# led_nightlight.net
KiCad netlist of a schematic drawn in EAGLE
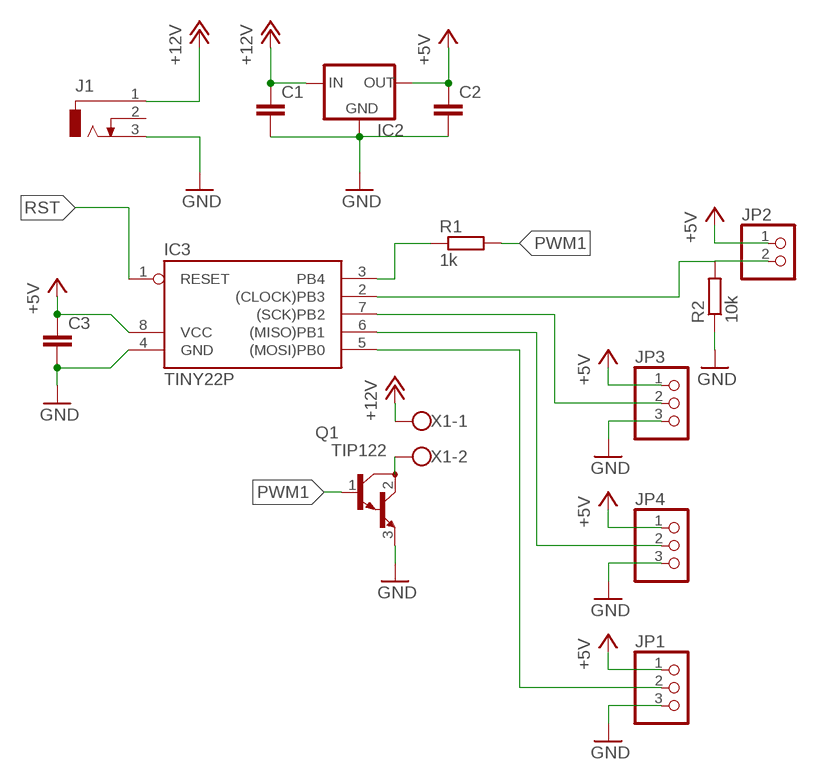
[diagram p0: schematic, sheet 1]

(export (version "E")
  (design (tool "Eeschema 10.0.6"))
  (components
    (comp (ref "C1")
      (value "C-EU025-024X044")
      (footprint "eagle-import:C025-024X044")
      (libsource (lib "eagle-import") (part "C-EU025-024X044"))
    )
    (comp (ref "C2")
      (value "C-EU025-024X044")
      (footprint "eagle-import:C025-024X044")
      (libsource (lib "eagle-import") (part "C-EU025-024X044"))
    )
    (comp (ref "C3")
      (value "C-EU025-024X044")
      (footprint "eagle-import:C025-024X044")
      (libsource (lib "eagle-import") (part "C-EU025-024X044"))
    )
    (comp (ref "IC2")
      (value "78XXL")
      (footprint "eagle-import:78XXL")
      (libsource (lib "eagle-import") (part "78XXL"))
    )
    (comp (ref "IC3")
      (value "TINY22P")
      (footprint "eagle-import:DIL08")
      (libsource (lib "eagle-import") (part "TINY22P"))
    )
    (comp (ref "J1")
      (value "DCJ0303")
      (footprint "eagle-import:DCJ0303")
      (libsource (lib "eagle-import") (part "DCJ0303"))
    )
    (comp (ref "JP1")
      (value "PINHD-1X3")
      (footprint "eagle-import:1X03")
      (libsource (lib "eagle-import") (part "PINHD-1X3"))
    )
    (comp (ref "JP2")
      (value "PINHD-1X2")
      (footprint "eagle-import:1X02")
      (libsource (lib "eagle-import") (part "PINHD-1X2"))
    )
    (comp (ref "JP3")
      (value "PINHD-1X3")
      (footprint "eagle-import:1X03")
      (libsource (lib "eagle-import") (part "PINHD-1X3"))
    )
    (comp (ref "JP4")
      (value "PINHD-1X3")
      (footprint "eagle-import:1X03")
      (libsource (lib "eagle-import") (part "PINHD-1X3"))
    )
    (comp (ref "Q1")
      (value "TIP122")
      (footprint "eagle-import:TO220")
      (libsource (lib "eagle-import") (part "TIP122"))
    )
    (comp (ref "R1")
      (value "1k")
      (footprint "eagle-import:0207_10")
      (libsource (lib "eagle-import") (part "R-EU_0207/10"))
    )
    (comp (ref "R2")
      (value "10k")
      (footprint "eagle-import:0207_10")
      (libsource (lib "eagle-import") (part "R-EU_0207/10"))
    )
    (comp (ref "X1")
      (value "W237-102")
      (footprint "eagle-import:W237-102")
      (fields (field (name "MPN") "237-102"))
      (libsource (lib "eagle-import") (part "W237-102"))
    )
  )
  (nets
    (net (code "1") (name "+5V") (class "Default")
      (node (ref "C2") (pin "1") (pinfunction "1_1") (pintype "passive"))
      (node (ref "C3") (pin "1") (pinfunction "1_1") (pintype "passive"))
      (node (ref "IC2") (pin "OUT") (pinfunction "OUT_OUT") (pintype "passive"))
      (node (ref "IC3") (pin "8") (pinfunction "VCC_8") (pintype "power_in"))
      (node (ref "JP1") (pin "1") (pinfunction "1_1") (pintype "passive"))
      (node (ref "JP2") (pin "1") (pinfunction "1_1") (pintype "passive"))
      (node (ref "JP3") (pin "1") (pinfunction "1_1") (pintype "passive"))
      (node (ref "JP4") (pin "1") (pinfunction "1_1") (pintype "passive"))
    )
    (net (code "2") (name "+12V") (class "Default")
      (node (ref "C1") (pin "1") (pinfunction "1_1") (pintype "passive"))
      (node (ref "IC2") (pin "IN") (pinfunction "IN_IN") (pintype "input"))
      (node (ref "J1") (pin "1") (pinfunction "1_1") (pintype "passive"))
      (node (ref "X1") (pin "1") (pinfunction "KL_1") (pintype "passive"))
    )
    (net (code "3") (name "GND") (class "Default")
      (node (ref "C1") (pin "2") (pinfunction "2_2") (pintype "passive"))
      (node (ref "C2") (pin "2") (pinfunction "2_2") (pintype "passive"))
      (node (ref "C3") (pin "2") (pinfunction "2_2") (pintype "passive"))
      (node (ref "IC2") (pin "GND") (pinfunction "GND_GND") (pintype "input"))
      (node (ref "IC3") (pin "4") (pinfunction "GND_4") (pintype "power_in"))
      (node (ref "J1") (pin "3") (pinfunction "3_3") (pintype "passive"))
      (node (ref "JP1") (pin "3") (pinfunction "3_3") (pintype "passive"))
      (node (ref "JP3") (pin "3") (pinfunction "3_3") (pintype "passive"))
      (node (ref "JP4") (pin "3") (pinfunction "3_3") (pintype "passive"))
      (node (ref "Q1") (pin "3") (pinfunction "E_3") (pintype "passive"))
      (node (ref "R2") (pin "1") (pinfunction "1_1") (pintype "passive"))
    )
    (net (code "4") (name "Net-(IC3-(CLOCK)PB3)") (class "Default")
      (node (ref "IC3") (pin "2") (pinfunction "(CLOCK)PB3_2") (pintype "bidirectional"))
      (node (ref "JP2") (pin "2") (pinfunction "2_2") (pintype "passive"))
      (node (ref "R2") (pin "2") (pinfunction "2_2") (pintype "passive"))
    )
    (net (code "5") (name "Net-(IC3-(MISO)PB1)") (class "Default")
      (node (ref "IC3") (pin "6") (pinfunction "(MISO)PB1_6") (pintype "bidirectional"))
      (node (ref "JP4") (pin "2") (pinfunction "2_2") (pintype "passive"))
    )
    (net (code "6") (name "Net-(IC3-(MOSI)PB0)") (class "Default")
      (node (ref "IC3") (pin "5") (pinfunction "(MOSI)PB0_5") (pintype "bidirectional"))
      (node (ref "JP1") (pin "2") (pinfunction "2_2") (pintype "passive"))
    )
    (net (code "7") (name "Net-(IC3-(SCK)PB2)") (class "Default")
      (node (ref "IC3") (pin "7") (pinfunction "(SCK)PB2_7") (pintype "bidirectional"))
      (node (ref "JP3") (pin "2") (pinfunction "2_2") (pintype "passive"))
    )
    (net (code "8") (name "Net-(IC3-PB4)") (class "Default")
      (node (ref "IC3") (pin "3") (pinfunction "PB4_3") (pintype "bidirectional"))
      (node (ref "R1") (pin "1") (pinfunction "1_1") (pintype "passive"))
    )
    (net (code "9") (name "Net-(Q1-C)") (class "Default")
      (node (ref "Q1") (pin "2") (pinfunction "C_2") (pintype "passive"))
      (node (ref "X1") (pin "2") (pinfunction "KL_2") (pintype "passive"))
    )
    (net (code "10") (name "PWM1") (class "Default")
      (node (ref "Q1") (pin "1") (pinfunction "B_1") (pintype "passive"))
      (node (ref "R1") (pin "2") (pinfunction "2_2") (pintype "passive"))
    )
    (net (code "11") (name "RST") (class "Default")
      (node (ref "IC3") (pin "1") (pinfunction "RESET_1") (pintype "input"))
    )
    (net (code "12") (name "unconnected-(J1-Pad2)") (class "Default")
      (node (ref "J1") (pin "2") (pinfunction "2_2") (pintype "passive"))
    )
  )
)
